# Sheet1.net
KiCad netlist of a schematic drawn in Altium Designer
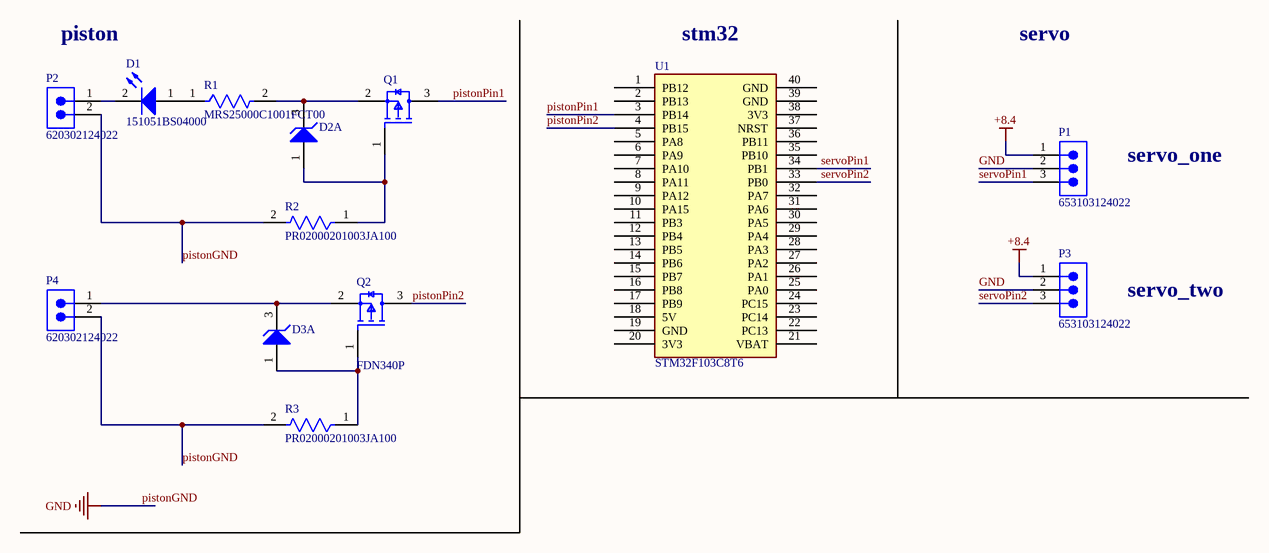
[diagram p0: Sheet1.SchDoc]

(export (version "E")
  (design (tool "Eeschema 10.0.6"))
  (components
    (comp (ref "D1")
      (value "151051BS04000")
      (footprint "WL-TMRC_D5.9H8.7")
      (libsource (lib "Altium Content Vault") (part "LED_Blue_1A-2K"))
    )
    (comp (ref "D2")
      (value "BZX84C6V2LT1G")
      (footprint "ONSC-SOT-23-3-318-08_V")
      (description "Zener Voltage Regulator, 225 mW, 3-Pin SOT-23, Pb-Free, Tape and Reel")
      (fields (field (name "MANUFACTURER") "On Semiconductor"))
      (libsource (lib "Altium Content Vault") (part "ONSC-A1K3-3"))
    )
    (comp (ref "D3")
      (value "BZX84C6V2LT1G")
      (footprint "ONSC-SOT-23-3-318-08_V")
      (description "Zener Voltage Regulator, 225 mW, 3-Pin SOT-23, Pb-Free, Tape and Reel")
      (fields (field (name "MANUFACTURER") "On Semiconductor"))
      (libsource (lib "Altium Content Vault") (part "ONSC-A1K3-3"))
    )
    (comp (ref "P1")
      (value "653103124022")
      (footprint "653103124022")
      (libsource (lib "Altium Content Vault") (part "Header_Male_1R_03P"))
    )
    (comp (ref "P2")
      (value "620302124022")
      (footprint "620302124022")
      (libsource (lib "Altium Content Vault") (part "Header_Male_1R_02P"))
    )
    (comp (ref "P3")
      (value "653103124022")
      (footprint "653103124022")
      (libsource (lib "Altium Content Vault") (part "Header_Male_1R_03P"))
    )
    (comp (ref "P4")
      (value "620302124022")
      (footprint "620302124022")
      (libsource (lib "Altium Content Vault") (part "Header_Male_1R_02P"))
    )
    (comp (ref "Q1")
      (value "FDN340P")
      (footprint "FP-527AG-MFG")
      (description "MOSFET P-CH 20V 2A SSOT3")
      (libsource (lib "Altium Content Vault") (part "d23f43cc42f60b967b7caccf14518fd"))
    )
    (comp (ref "Q2")
      (value "FDN340P")
      (footprint "FP-527AG-MFG")
      (description "MOSFET P-CH 20V 2A SSOT3")
      (libsource (lib "Altium Content Vault") (part "d23f43cc42f60b967b7caccf14518fd"))
    )
    (comp (ref "R1")
      (value "MRS25000C1001FCT00")
      (footprint "FP-MRS25-MFG")
      (description "RES 1K OHM 0.6W 1% AXIAL")
      (fields (field (name "TOLERANCE") "1%"))
      (libsource (lib "Altium Content Vault") (part "1029c3af85768c4190bb7ad29bc67b5"))
    )
    (comp (ref "R2")
      (value "PR02000201003JA100")
      (footprint "FP-PR02000201003JA100-MFG")
      (fields (field (name "TOLERANCE") "5%"))
      (libsource (lib "Altium Content Vault") (part "1029c3af85768c4190bb7ad29bc67b5"))
    )
    (comp (ref "R3")
      (value "PR02000201003JA100")
      (footprint "FP-PR02000201003JA100-MFG")
      (fields (field (name "TOLERANCE") "5%"))
      (libsource (lib "Altium Content Vault") (part "1029c3af85768c4190bb7ad29bc67b5"))
    )
    (comp (ref "U1")
      (value "STM32F103C8T6")
      (footprint "Stm32 BluePill")
      (description "Designed By @Alixahedi")
      (libsource (lib "Stm32 Blue Pill") (part "BluePill"))
    )
  )
  (nets
    (net (code "1") (name "+8.4") (class "Default")
      (node (ref "P1") (pin "1") (pinfunction "1_1") (pintype "passive"))
      (node (ref "P3") (pin "1") (pinfunction "1_1") (pintype "passive"))
    )
    (net (code "2") (name "/pistonPin1") (class "Default")
      (node (ref "Q1") (pin "3") (pinfunction "D_3") (pintype "passive"))
      (node (ref "U1") (pin "3") (pinfunction "PB14_3") (pintype "passive"))
    )
    (net (code "3") (name "/pistonPin2") (class "Default")
      (node (ref "Q2") (pin "3") (pinfunction "D_3") (pintype "passive"))
      (node (ref "U1") (pin "4") (pinfunction "PB15_4") (pintype "passive"))
    )
    (net (code "4") (name "/servoPin1") (class "Default")
      (node (ref "P1") (pin "3") (pinfunction "3_3") (pintype "passive"))
      (node (ref "U1") (pin "34") (pinfunction "PB1_34") (pintype "passive"))
    )
    (net (code "5") (name "/servoPin2") (class "Default")
      (node (ref "P3") (pin "3") (pinfunction "3_3") (pintype "passive"))
      (node (ref "U1") (pin "33") (pinfunction "PB0_33") (pintype "passive"))
    )
    (net (code "6") (name "GND") (class "Default")
      (node (ref "P1") (pin "2") (pinfunction "2_2") (pintype "passive"))
      (node (ref "P2") (pin "2") (pinfunction "2_2") (pintype "passive"))
      (node (ref "P3") (pin "2") (pinfunction "2_2") (pintype "passive"))
      (node (ref "P4") (pin "2") (pinfunction "2_2") (pintype "passive"))
      (node (ref "R2") (pin "2") (pinfunction "2_2") (pintype "passive"))
      (node (ref "R3") (pin "2") (pinfunction "2_2") (pintype "passive"))
    )
    (net (code "7") (name "Net-(D1-A)") (class "Default")
      (node (ref "D1") (pin "1") (pinfunction "A_1") (pintype "passive"))
      (node (ref "R1") (pin "1") (pinfunction "1_1") (pintype "passive"))
    )
    (net (code "8") (name "Net-(D1-K)") (class "Default")
      (node (ref "D1") (pin "2") (pinfunction "K_2") (pintype "passive"))
      (node (ref "P2") (pin "1") (pinfunction "1_1") (pintype "passive"))
    )
    (net (code "9") (name "Net-(D2A-A)") (class "Default")
      (node (ref "D2") (pin "1") (pinfunction "A_1") (pintype "passive"))
      (node (ref "Q1") (pin "1") (pinfunction "G_1") (pintype "passive"))
      (node (ref "R2") (pin "1") (pinfunction "1_1") (pintype "passive"))
    )
    (net (code "10") (name "Net-(D2A-K)") (class "Default")
      (node (ref "D2") (pin "3") (pinfunction "K_3") (pintype "passive"))
      (node (ref "Q1") (pin "2") (pinfunction "S_2") (pintype "passive"))
      (node (ref "R1") (pin "2") (pinfunction "2_2") (pintype "passive"))
    )
    (net (code "11") (name "Net-(D3A-A)") (class "Default")
      (node (ref "D3") (pin "1") (pinfunction "A_1") (pintype "passive"))
      (node (ref "Q2") (pin "1") (pinfunction "G_1") (pintype "passive"))
      (node (ref "R3") (pin "1") (pinfunction "1_1") (pintype "passive"))
    )
    (net (code "12") (name "Net-(D3A-K)") (class "Default")
      (node (ref "D3") (pin "3") (pinfunction "K_3") (pintype "passive"))
      (node (ref "P4") (pin "1") (pinfunction "1_1") (pintype "passive"))
      (node (ref "Q2") (pin "2") (pinfunction "S_2") (pintype "passive"))
    )
    (net (code "13") (name "unconnected-(U1-3V3-Pad20)") (class "Default")
      (node (ref "U1") (pin "20") (pinfunction "3V3_20") (pintype "passive"))
    )
    (net (code "14") (name "unconnected-(U1-3V3-Pad38)") (class "Default")
      (node (ref "U1") (pin "38") (pinfunction "3V3_38") (pintype "passive"))
    )
    (net (code "15") (name "unconnected-(U1-5V-Pad18)") (class "Default")
      (node (ref "U1") (pin "18") (pinfunction "5V_18") (pintype "passive"))
    )
    (net (code "16") (name "unconnected-(U1-GND-Pad19)") (class "Default")
      (node (ref "U1") (pin "19") (pinfunction "GND_19") (pintype "passive"))
    )
    (net (code "17") (name "unconnected-(U1-GND-Pad39)") (class "Default")
      (node (ref "U1") (pin "39") (pinfunction "GND_39") (pintype "passive"))
    )
    (net (code "18") (name "unconnected-(U1-GND-Pad40)") (class "Default")
      (node (ref "U1") (pin "40") (pinfunction "GND_40") (pintype "passive"))
    )
    (net (code "19") (name "unconnected-(U1-NRST-Pad37)") (class "Default")
      (node (ref "U1") (pin "37") (pinfunction "NRST_37") (pintype "passive"))
    )
    (net (code "20") (name "unconnected-(U1-PA0-Pad25)") (class "Default")
      (node (ref "U1") (pin "25") (pinfunction "PA0_25") (pintype "passive"))
    )
    (net (code "21") (name "unconnected-(U1-PA1-Pad26)") (class "Default")
      (node (ref "U1") (pin "26") (pinfunction "PA1_26") (pintype "passive"))
    )
    (net (code "22") (name "unconnected-(U1-PA2-Pad27)") (class "Default")
      (node (ref "U1") (pin "27") (pinfunction "PA2_27") (pintype "passive"))
    )
    (net (code "23") (name "unconnected-(U1-PA3-Pad28)") (class "Default")
      (node (ref "U1") (pin "28") (pinfunction "PA3_28") (pintype "passive"))
    )
    (net (code "24") (name "unconnected-(U1-PA4-Pad29)") (class "Default")
      (node (ref "U1") (pin "29") (pinfunction "PA4_29") (pintype "passive"))
    )
    (net (code "25") (name "unconnected-(U1-PA5-Pad30)") (class "Default")
      (node (ref "U1") (pin "30") (pinfunction "PA5_30") (pintype "passive"))
    )
    (net (code "26") (name "unconnected-(U1-PA6-Pad31)") (class "Default")
      (node (ref "U1") (pin "31") (pinfunction "PA6_31") (pintype "passive"))
    )
    (net (code "27") (name "unconnected-(U1-PA7-Pad32)") (class "Default")
      (node (ref "U1") (pin "32") (pinfunction "PA7_32") (pintype "passive"))
    )
    (net (code "28") (name "unconnected-(U1-PA8-Pad5)") (class "Default")
      (node (ref "U1") (pin "5") (pinfunction "PA8_5") (pintype "passive"))
    )
    (net (code "29") (name "unconnected-(U1-PA9-Pad6)") (class "Default")
      (node (ref "U1") (pin "6") (pinfunction "PA9_6") (pintype "passive"))
    )
    (net (code "30") (name "unconnected-(U1-PA10-Pad7)") (class "Default")
      (node (ref "U1") (pin "7") (pinfunction "PA10_7") (pintype "passive"))
    )
    (net (code "31") (name "unconnected-(U1-PA11-Pad8)") (class "Default")
      (node (ref "U1") (pin "8") (pinfunction "PA11_8") (pintype "passive"))
    )
    (net (code "32") (name "unconnected-(U1-PA12-Pad9)") (class "Default")
      (node (ref "U1") (pin "9") (pinfunction "PA12_9") (pintype "passive"))
    )
    (net (code "33") (name "unconnected-(U1-PA15-Pad10)") (class "Default")
      (node (ref "U1") (pin "10") (pinfunction "PA15_10") (pintype "passive"))
    )
    (net (code "34") (name "unconnected-(U1-PB3-Pad11)") (class "Default")
      (node (ref "U1") (pin "11") (pinfunction "PB3_11") (pintype "passive"))
    )
    (net (code "35") (name "unconnected-(U1-PB4-Pad12)") (class "Default")
      (node (ref "U1") (pin "12") (pinfunction "PB4_12") (pintype "passive"))
    )
    (net (code "36") (name "unconnected-(U1-PB5-Pad13)") (class "Default")
      (node (ref "U1") (pin "13") (pinfunction "PB5_13") (pintype "passive"))
    )
    (net (code "37") (name "unconnected-(U1-PB6-Pad14)") (class "Default")
      (node (ref "U1") (pin "14") (pinfunction "PB6_14") (pintype "passive"))
    )
    (net (code "38") (name "unconnected-(U1-PB7-Pad15)") (class "Default")
      (node (ref "U1") (pin "15") (pinfunction "PB7_15") (pintype "passive"))
    )
    (net (code "39") (name "unconnected-(U1-PB8-Pad16)") (class "Default")
      (node (ref "U1") (pin "16") (pinfunction "PB8_16") (pintype "passive"))
    )
    (net (code "40") (name "unconnected-(U1-PB9-Pad17)") (class "Default")
      (node (ref "U1") (pin "17") (pinfunction "PB9_17") (pintype "passive"))
    )
    (net (code "41") (name "unconnected-(U1-PB10-Pad35)") (class "Default")
      (node (ref "U1") (pin "35") (pinfunction "PB10_35") (pintype "passive"))
    )
    (net (code "42") (name "unconnected-(U1-PB11-Pad36)") (class "Default")
      (node (ref "U1") (pin "36") (pinfunction "PB11_36") (pintype "passive"))
    )
    (net (code "43") (name "unconnected-(U1-PB12-Pad1)") (class "Default")
      (node (ref "U1") (pin "1") (pinfunction "PB12_1") (pintype "passive"))
    )
    (net (code "44") (name "unconnected-(U1-PB13-Pad2)") (class "Default")
      (node (ref "U1") (pin "2") (pinfunction "PB13_2") (pintype "passive"))
    )
    (net (code "45") (name "unconnected-(U1-PC13-Pad22)") (class "Default")
      (node (ref "U1") (pin "22") (pinfunction "PC13_22") (pintype "passive"))
    )
    (net (code "46") (name "unconnected-(U1-PC14-Pad23)") (class "Default")
      (node (ref "U1") (pin "23") (pinfunction "PC14_23") (pintype "passive"))
    )
    (net (code "47") (name "unconnected-(U1-PC15-Pad24)") (class "Default")
      (node (ref "U1") (pin "24") (pinfunction "PC15_24") (pintype "passive"))
    )
    (net (code "48") (name "unconnected-(U1-VBAT-Pad21)") (class "Default")
      (node (ref "U1") (pin "21") (pinfunction "VBAT_21") (pintype "passive"))
    )
  )
)
